# FSP-485.net
KiCad netlist of a schematic drawn in Altium Designer
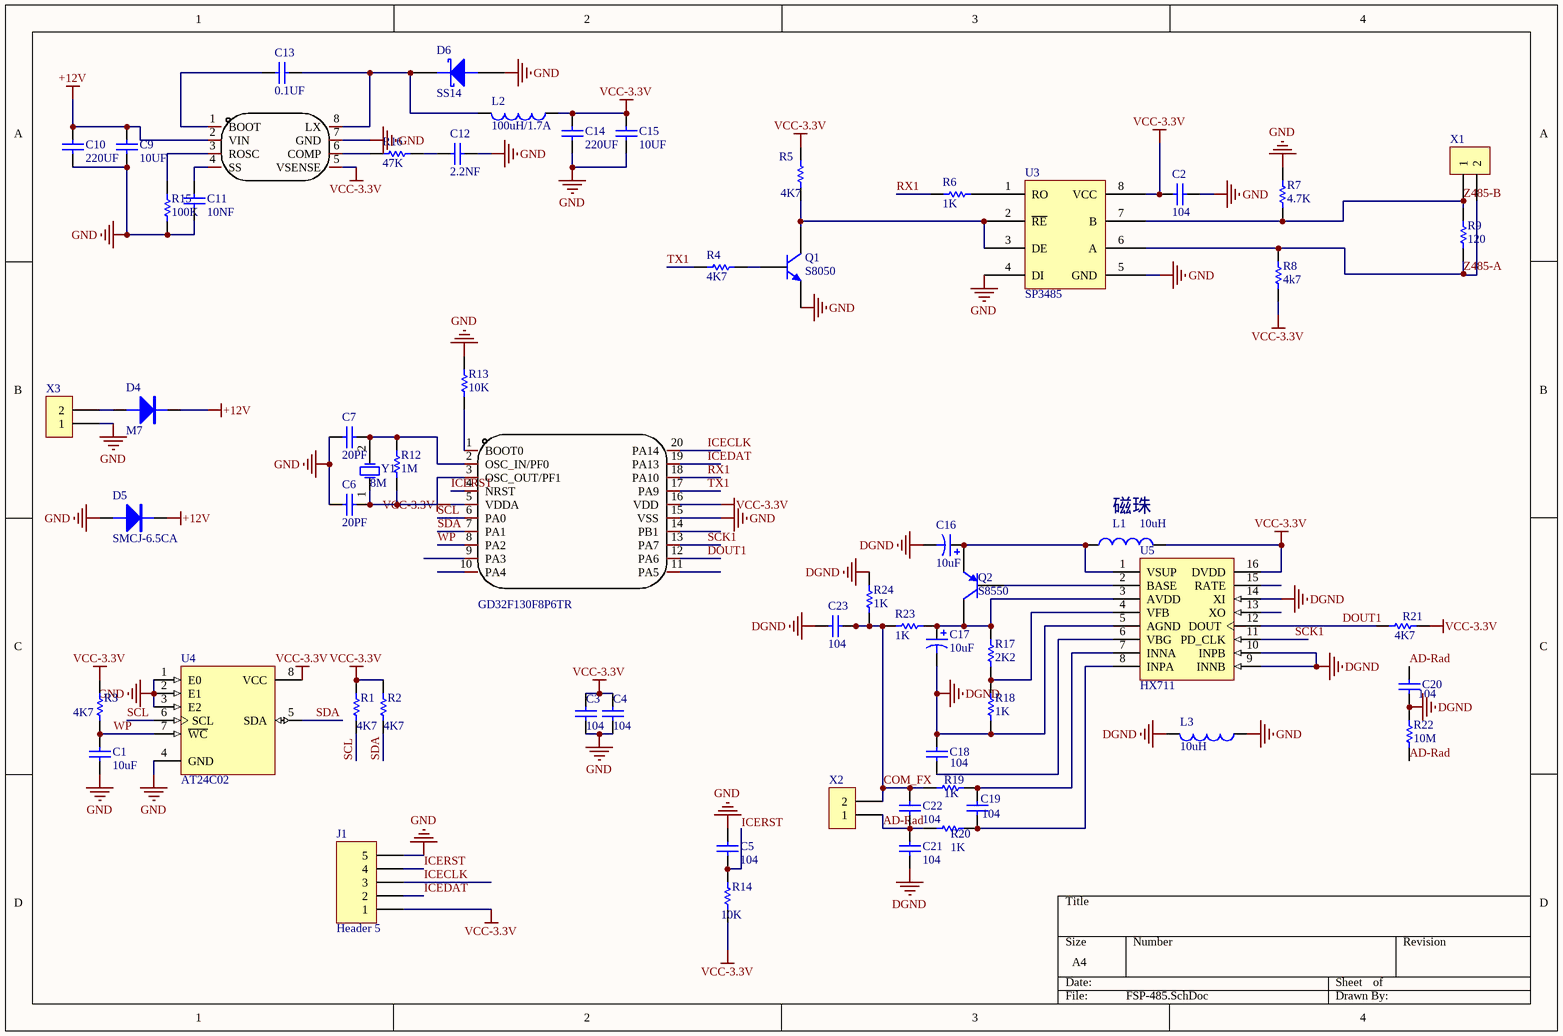
[diagram p0: FSP-485.SchDoc]

(export (version "E")
  (design (tool "Eeschema 10.0.6"))
  (components
    (comp (ref "C1")
      (value "10uF")
      (footprint "R0603")
      (description "Capacitor")
      (fields (field (name "Comment") "10uf") (field (name "PUBLISHER") "Altium Limited"))
      (libsource (lib "Miscellaneous Devices") (part "Cap"))
    )
    (comp (ref "C2")
      (value "104")
      (footprint "R0603")
      (description "Capacitor")
      (fields (field (name "PUBLISHER") "Altium Limited"))
      (libsource (lib "Miscellaneous Devices") (part "Cap"))
    )
    (comp (ref "C3")
      (value "104")
      (footprint "R0603")
      (description "Capacitor")
      (fields (field (name "PUBLISHER") "Altium Limited"))
      (libsource (lib "Miscellaneous Devices") (part "Cap"))
    )
    (comp (ref "C4")
      (value "104")
      (footprint "R0603")
      (description "Capacitor")
      (fields (field (name "PUBLISHER") "Altium Limited"))
      (libsource (lib "Miscellaneous Devices") (part "Cap"))
    )
    (comp (ref "C5")
      (value "104")
      (footprint "R0603")
      (description "Capacitor")
      (fields (field (name "PUBLISHER") "Altium Limited"))
      (libsource (lib "Miscellaneous Devices") (part "Cap"))
    )
    (comp (ref "C6")
      (value "20PF")
      (footprint "0805C")
      (description "Capacitor")
      (fields (field (name "PUBLISHER") "Altium Limited"))
      (libsource (lib "Wire Test") (part "Cap"))
    )
    (comp (ref "C7")
      (value "20PF")
      (footprint "0805C")
      (description "Capacitor")
      (fields (field (name "PUBLISHER") "Altium Limited"))
      (libsource (lib "Wire Test") (part "Cap"))
    )
    (comp (ref "C9")
      (value "10UF")
      (footprint "R0603")
      (description "Capacitor")
      (fields (field (name "PUBLISHER") "Altium Limited"))
      (libsource (lib "Wire Test") (part "Cap"))
    )
    (comp (ref "C10")
      (value "220UF")
      (footprint "CAP+_47UF_5X5")
      (description "Capacitor")
      (fields (field (name "PUBLISHER") "Altium Limited"))
      (libsource (lib "Wire Test") (part "Cap"))
    )
    (comp (ref "C11")
      (value "10NF")
      (footprint "R0603")
      (description "Capacitor")
      (fields (field (name "PUBLISHER") "Altium Limited"))
      (libsource (lib "Wire Test") (part "Cap"))
    )
    (comp (ref "C12")
      (value "2.2NF")
      (footprint "R0603")
      (description "Capacitor")
      (fields (field (name "PUBLISHER") "Altium Limited"))
      (libsource (lib "Wire Test") (part "Cap"))
    )
    (comp (ref "C13")
      (value "0.1UF")
      (footprint "R0603")
      (description "Capacitor")
      (fields (field (name "PUBLISHER") "Altium Limited"))
      (libsource (lib "Wire Test") (part "Cap"))
    )
    (comp (ref "C14")
      (value "220UF")
      (footprint "DAN-DIAN-RONG-1210")
      (description "Capacitor")
      (fields (field (name "PUBLISHER") "Altium Limited"))
      (libsource (lib "Wire Test") (part "Cap"))
    )
    (comp (ref "C15")
      (value "10UF")
      (footprint "R0603")
      (description "Capacitor")
      (fields (field (name "PUBLISHER") "Altium Limited"))
      (libsource (lib "Wire Test") (part "Cap"))
    )
    (comp (ref "C16")
      (value "10uF")
      (footprint "R0603")
      (description "Polarized Capacitor (Surface Mount)")
      (fields (field (name "Comment") "10uf") (field (name "PUBLISHER") "Altium Limited"))
      (libsource (lib "Miscellaneous Devices") (part "Cap Pol3"))
    )
    (comp (ref "C17")
      (value "10uF")
      (footprint "R0603")
      (description "Polarized Capacitor (Surface Mount)")
      (fields (field (name "Comment") "10uf") (field (name "PUBLISHER") "Altium Limited"))
      (libsource (lib "Miscellaneous Devices") (part "Cap Pol3"))
    )
    (comp (ref "C18")
      (value "104")
      (footprint "R0603")
      (description "Capacitor")
      (fields (field (name "PUBLISHER") "Altium Limited"))
      (libsource (lib "Miscellaneous Devices") (part "Cap"))
    )
    (comp (ref "C19")
      (value "104")
      (footprint "R0603")
      (description "Capacitor")
      (fields (field (name "PUBLISHER") "Altium Limited"))
      (libsource (lib "Miscellaneous Devices") (part "Cap"))
    )
    (comp (ref "C20")
      (value "104")
      (footprint "R0603")
      (description "Capacitor")
      (fields (field (name "PUBLISHER") "Altium Limited"))
      (libsource (lib "Miscellaneous Devices") (part "Cap"))
    )
    (comp (ref "C21")
      (value "104")
      (footprint "R0603")
      (description "Capacitor")
      (fields (field (name "PUBLISHER") "Altium Limited"))
      (libsource (lib "Miscellaneous Devices") (part "Cap"))
    )
    (comp (ref "C22")
      (value "104")
      (footprint "R0603")
      (description "Capacitor")
      (fields (field (name "PUBLISHER") "Altium Limited"))
      (libsource (lib "Miscellaneous Devices") (part "Cap"))
    )
    (comp (ref "C23")
      (value "104")
      (footprint "R0603")
      (description "Capacitor")
      (fields (field (name "PUBLISHER") "Altium Limited"))
      (libsource (lib "Miscellaneous Devices") (part "Cap"))
    )
    (comp (ref "D4")
      (value "M7")
      (footprint "DIODE")
      (description "Diode")
      (libsource (lib "*") (part "DIODE"))
    )
    (comp (ref "D5")
      (value "SMCJ-6.5CA")
      (footprint "DIODE")
      (description "Diode")
      (libsource (lib "*") (part "DIODE"))
    )
    (comp (ref "D6")
      (value "SS14")
      (footprint "DIODE")
      (description "Schottky Diode")
      (libsource (lib "*") (part "DIODE SCHOTTKY"))
    )
    (comp (ref "J1")
      (value "Header 5")
      (footprint "HDR1X5")
      (description "Header, 5-Pin")
      (fields (field (name "PUBLISHER") "Altium Limited"))
      (libsource (lib "Miscellaneous Connectors") (part "Header 5"))
    )
    (comp (ref "L1")
      (value "10uH")
      (footprint "R0603")
      (description "Inductor")
      (fields (field (name "PUBLISHER") "Altium Limited"))
      (libsource (lib "") (part "Inductor_1"))
    )
    (comp (ref "L2")
      (value "100uH/1.7A")
      (footprint "SMD-6*6MM")
      (description "Inductor")
      (fields (field (name "PUBLISHER") "Altium Limited"))
      (libsource (lib "Miscellaneous Devices") (part "Inductor"))
    )
    (comp (ref "L3")
      (value "10uH")
      (footprint "R0603")
      (description "Inductor")
      (fields (field (name "PUBLISHER") "Altium Limited"))
      (libsource (lib "Miscellaneous Devices") (part "Inductor"))
    )
    (comp (ref "Q1")
      (value "S8050")
      (footprint "Q8050")
      (description "NPN General Purpose Amplifier")
      (fields (field (name "PUBLISHER") "Altium Limited"))
      (libsource (lib "*") (part "2N3904"))
    )
    (comp (ref "Q2")
      (value "S8550")
      (footprint "Q8550")
      (description "PNP General Purpose Amplifier")
      (fields (field (name "PUBLISHER") "Altium Limited"))
      (libsource (lib "Miscellaneous Devices") (part "2N3906"))
    )
    (comp (ref "R1")
      (value "4K7")
      (footprint "R0603")
      (description "Resistor")
      (fields (field (name "PUBLISHER") "Altium Limited"))
      (libsource (lib "Wire Test") (part "Res1"))
    )
    (comp (ref "R2")
      (value "4K7")
      (footprint "R0603")
      (description "Resistor")
      (fields (field (name "PUBLISHER") "Altium Limited"))
      (libsource (lib "Wire Test") (part "Res1"))
    )
    (comp (ref "R3")
      (value "4K7")
      (footprint "R0603")
      (description "Resistor")
      (fields (field (name "PUBLISHER") "Altium Limited"))
      (libsource (lib "Wire Test") (part "Res1"))
    )
    (comp (ref "R4")
      (value "4K7")
      (footprint "R0603")
      (description "Resistor")
      (fields (field (name "PUBLISHER") "Altium Limited"))
      (libsource (lib "*") (part "Res1"))
    )
    (comp (ref "R5")
      (value "4K7")
      (footprint "R0603")
      (description "Resistor")
      (fields (field (name "PUBLISHER") "Altium Limited"))
      (libsource (lib "*") (part "Res1"))
    )
    (comp (ref "R6")
      (value "1K")
      (footprint "R0603")
      (description "Resistor")
      (fields (field (name "PUBLISHER") "Altium Limited"))
      (libsource (lib "*") (part "Res1"))
    )
    (comp (ref "R7")
      (value "4.7K")
      (footprint "R0603")
      (description "Resistor")
      (fields (field (name "Comment") "4K7") (field (name "PUBLISHER") "Altium Limited"))
      (libsource (lib "*") (part "Res1"))
    )
    (comp (ref "R8")
      (value "4k7")
      (footprint "R0603")
      (description "Resistor")
      (fields (field (name "Comment") "4K7") (field (name "PUBLISHER") "Altium Limited"))
      (libsource (lib "*") (part "Res1"))
    )
    (comp (ref "R9")
      (value "120")
      (footprint "R0603")
      (description "Resistor")
      (fields (field (name "PUBLISHER") "Altium Limited"))
      (libsource (lib "*") (part "Res1"))
    )
    (comp (ref "R12")
      (value "1M")
      (footprint "R0603")
      (description "Resistor")
      (fields (field (name "PUBLISHER") "Altium Limited"))
      (libsource (lib "Wire Test") (part "Res1"))
    )
    (comp (ref "R13")
      (value "10K")
      (footprint "R0603")
      (description "Resistor")
      (fields (field (name "PUBLISHER") "Altium Limited"))
      (libsource (lib "Wire Test") (part "Res1"))
    )
    (comp (ref "R14")
      (value "10K")
      (footprint "R0603")
      (description "Resistor")
      (fields (field (name "PUBLISHER") "Altium Limited"))
      (libsource (lib "*") (part "Res1"))
    )
    (comp (ref "R15")
      (value "100K")
      (footprint "R0603")
      (description "Resistor")
      (fields (field (name "PUBLISHER") "Altium Limited"))
      (libsource (lib "Wire Test") (part "Res1"))
    )
    (comp (ref "R16")
      (value "47K")
      (footprint "R0603")
      (description "Resistor")
      (fields (field (name "PUBLISHER") "Altium Limited"))
      (libsource (lib "Wire Test") (part "Res1"))
    )
    (comp (ref "R17")
      (value "2K2")
      (footprint "R0603")
      (description "Resistor")
      (fields (field (name "PUBLISHER") "Altium Limited"))
      (libsource (lib "Wire Test") (part "Res1"))
    )
    (comp (ref "R18")
      (value "1K")
      (footprint "R0603")
      (description "Resistor")
      (fields (field (name "PUBLISHER") "Altium Limited"))
      (libsource (lib "Wire Test") (part "Res1"))
    )
    (comp (ref "R19")
      (value "1K")
      (footprint "R0603")
      (description "Resistor")
      (fields (field (name "PUBLISHER") "Altium Limited"))
      (libsource (lib "Wire Test") (part "Res1"))
    )
    (comp (ref "R20")
      (value "1K")
      (footprint "R0603")
      (description "Resistor")
      (fields (field (name "PUBLISHER") "Altium Limited"))
      (libsource (lib "Wire Test") (part "Res1"))
    )
    (comp (ref "R21")
      (value "4K7")
      (footprint "R0603")
      (description "Resistor")
      (fields (field (name "PUBLISHER") "Altium Limited"))
      (libsource (lib "Wire Test") (part "Res1"))
    )
    (comp (ref "R22")
      (value "10M")
      (footprint "R0603")
      (description "Resistor")
      (fields (field (name "PUBLISHER") "Altium Limited"))
      (libsource (lib "Wire Test") (part "Res1"))
    )
    (comp (ref "R23")
      (value "1K")
      (footprint "R0603")
      (description "Resistor")
      (fields (field (name "PUBLISHER") "Altium Limited"))
      (libsource (lib "Wire Test") (part "Res1"))
    )
    (comp (ref "R24")
      (value "1K")
      (footprint "R0603")
      (description "Resistor")
      (fields (field (name "PUBLISHER") "Altium Limited"))
      (libsource (lib "Wire Test") (part "Res1"))
    )
    (comp (ref "U1")
      (value "GD32F130F8P6TR")
      (footprint "GD32F130F8P6TR")
      (fields (field (name "MANUFACTURER") "GigaDevice(兆易创新)"))
      (libsource (lib "altium-import") (part "root_0_GD32F130F8P6TR_"))
    )
    (comp (ref "U2")
      (value "TPS5403DR")
      (footprint "TPS5403DR")
      (fields (field (name "MANUFACTURER") "TI(德州仪器)"))
      (libsource (lib "altium-import") (part "root_0_TPS5403DR_"))
    )
    (comp (ref "U3") (value "SP3485") (footprint "MAX485") (libsource (lib "金龙107原理图封装库") (part "MAX485")))
    (comp (ref "U4")
      (value "AT24C02")
      (footprint "AT24C02")
      (description "2Kbit Serial I睠 Bus EEPROM")
      (fields (field (name "PUBLISHER") "Altium Limited"))
      (libsource (lib "ST Memory EEPROM Serial") (part "M24C02BN6"))
    )
    (comp (ref "U5") (value "HX711") (footprint "HX711") (libsource (lib "微电脑分装机_1") (part "HX711")))
    (comp (ref "X1")
      (value "~")
      (footprint "CON-2.54mm*2")
      (description "Connector")
      (libsource (lib "*") (part "CON2"))
    )
    (comp (ref "X2")
      (value "~")
      (footprint "CON-2.54mm*2")
      (description "Connector")
      (libsource (lib "") (part "CON2_1"))
    )
    (comp (ref "X3")
      (value "~")
      (footprint "CON-2.54mm*2")
      (description "Connector")
      (libsource (lib "") (part "CON2_1"))
    )
    (comp (ref "Y1")
      (value "8M")
      (footprint "XTAL-T")
      (description "Crystal Oscillator")
      (fields (field (name "PUBLISHER") "Altium Limited"))
      (libsource (lib "Miscellaneous Devices") (part "XTAL"))
    )
  )
  (nets
    (net (code "1") (name "+12V") (class "Default")
      (node (ref "C10") (pin "1") (pinfunction "1_1") (pintype "passive"))
      (node (ref "C9") (pin "1") (pinfunction "1_1") (pintype "passive"))
      (node (ref "D4") (pin "2") (pinfunction "K_2") (pintype "passive"))
      (node (ref "D5") (pin "2") (pinfunction "K_2") (pintype "passive"))
      (node (ref "U2") (pin "2") (pinfunction "VIN_2") (pintype "passive"))
    )
    (net (code "2") (name "/AD-Rad") (class "Default")
      (node (ref "C20") (pin "1") (pinfunction "1_1") (pintype "passive"))
      (node (ref "C21") (pin "1") (pinfunction "1_1") (pintype "passive"))
      (node (ref "C22") (pin "1") (pinfunction "1_1") (pintype "passive"))
      (node (ref "R20") (pin "1") (pinfunction "1_1") (pintype "passive"))
      (node (ref "R22") (pin "1") (pinfunction "1_1") (pintype "passive"))
      (node (ref "X2") (pin "1") (pinfunction "1_1") (pintype "passive"))
    )
    (net (code "3") (name "/COM_FX") (class "Default")
      (node (ref "C22") (pin "2") (pinfunction "2_2") (pintype "passive"))
      (node (ref "C23") (pin "1") (pinfunction "1_1") (pintype "passive"))
      (node (ref "R19") (pin "1") (pinfunction "1_1") (pintype "passive"))
      (node (ref "R23") (pin "1") (pinfunction "1_1") (pintype "passive"))
      (node (ref "R24") (pin "2") (pinfunction "2_2") (pintype "passive"))
      (node (ref "X2") (pin "2") (pinfunction "2_2") (pintype "passive"))
    )
    (net (code "4") (name "/DOUT1") (class "Default")
      (node (ref "R21") (pin "2") (pinfunction "2_2") (pintype "passive"))
      (node (ref "U1") (pin "12") (pinfunction "PA6_12") (pintype "passive"))
      (node (ref "U5") (pin "12") (pinfunction "DOUT_12") (pintype "passive"))
    )
    (net (code "5") (name "/ICECLK") (class "Default")
      (node (ref "J1") (pin "3") (pinfunction "3_3") (pintype "passive"))
      (node (ref "U1") (pin "20") (pinfunction "PA14_20") (pintype "passive"))
    )
    (net (code "6") (name "/ICEDAT") (class "Default")
      (node (ref "J1") (pin "2") (pinfunction "2_2") (pintype "passive"))
      (node (ref "U1") (pin "19") (pinfunction "PA13_19") (pintype "passive"))
    )
    (net (code "7") (name "/ICERST") (class "Default")
      (node (ref "C5") (pin "1") (pinfunction "1_1") (pintype "passive"))
      (node (ref "J1") (pin "4") (pinfunction "4_4") (pintype "passive"))
      (node (ref "R14") (pin "1") (pinfunction "1_1") (pintype "passive"))
      (node (ref "U1") (pin "4") (pinfunction "NRST_4") (pintype "passive"))
    )
    (net (code "8") (name "/RX1") (class "Default")
      (node (ref "R6") (pin "2") (pinfunction "2_2") (pintype "passive"))
      (node (ref "U1") (pin "18") (pinfunction "PA10_18") (pintype "passive"))
    )
    (net (code "9") (name "/SCK1") (class "Default")
      (node (ref "U1") (pin "13") (pinfunction "PA7_13") (pintype "passive"))
      (node (ref "U5") (pin "11") (pinfunction "PD_CLK_11") (pintype "input"))
    )
    (net (code "10") (name "/SCL") (class "Default")
      (node (ref "R1") (pin "1") (pinfunction "1_1") (pintype "passive"))
      (node (ref "U1") (pin "6") (pinfunction "PA0_6") (pintype "passive"))
      (node (ref "U4") (pin "6") (pinfunction "SCL_6") (pintype "input"))
    )
    (net (code "11") (name "/SDA") (class "Default")
      (node (ref "R2") (pin "1") (pinfunction "1_1") (pintype "passive"))
      (node (ref "U1") (pin "7") (pinfunction "PA1_7") (pintype "passive"))
      (node (ref "U4") (pin "5") (pinfunction "SDA_5") (pintype "bidirectional"))
    )
    (net (code "12") (name "/TX1") (class "Default")
      (node (ref "R4") (pin "1") (pinfunction "1_1") (pintype "passive"))
      (node (ref "U1") (pin "17") (pinfunction "PA9_17") (pintype "passive"))
    )
    (net (code "13") (name "/WP") (class "Default")
      (node (ref "C1") (pin "2") (pinfunction "2_2") (pintype "passive"))
      (node (ref "R3") (pin "1") (pinfunction "1_1") (pintype "passive"))
      (node (ref "U1") (pin "8") (pinfunction "PA2_8") (pintype "passive"))
      (node (ref "U4") (pin "7") (pinfunction "~{WC}_7") (pintype "input"))
    )
    (net (code "14") (name "/Z485-A") (class "Default")
      (node (ref "R8") (pin "1") (pinfunction "1_1") (pintype "passive"))
      (node (ref "R9") (pin "2") (pinfunction "2_2") (pintype "passive"))
      (node (ref "U3") (pin "6") (pinfunction "A_6") (pintype "open_emitter"))
      (node (ref "X1") (pin "2") (pinfunction "2_2") (pintype "passive"))
    )
    (net (code "15") (name "/Z485-B") (class "Default")
      (node (ref "R7") (pin "1") (pinfunction "1_1") (pintype "passive"))
      (node (ref "R9") (pin "1") (pinfunction "1_1") (pintype "passive"))
      (node (ref "U3") (pin "7") (pinfunction "B_7") (pintype "open_emitter"))
      (node (ref "X1") (pin "1") (pinfunction "1_1") (pintype "passive"))
    )
    (net (code "16") (name "DGND") (class "Default")
      (node (ref "C16") (pin "2") (pinfunction "2_2") (pintype "passive"))
      (node (ref "C17") (pin "2") (pinfunction "2_2") (pintype "passive"))
      (node (ref "C18") (pin "2") (pinfunction "2_2") (pintype "passive"))
      (node (ref "C20") (pin "2") (pinfunction "2_2") (pintype "passive"))
      (node (ref "C21") (pin "2") (pinfunction "2_2") (pintype "passive"))
      (node (ref "C23") (pin "2") (pinfunction "2_2") (pintype "passive"))
      (node (ref "L3") (pin "1") (pinfunction "1_1") (pintype "passive"))
      (node (ref "R18") (pin "2") (pinfunction "2_2") (pintype "passive"))
      (node (ref "R22") (pin "2") (pinfunction "2_2") (pintype "passive"))
      (node (ref "R24") (pin "1") (pinfunction "1_1") (pintype "passive"))
      (node (ref "U5") (pin "10") (pinfunction "INPB_10") (pintype "input"))
      (node (ref "U5") (pin "14") (pinfunction "XI_14") (pintype "input"))
      (node (ref "U5") (pin "5") (pinfunction "AGND_5") (pintype "tri_state"))
      (node (ref "U5") (pin "9") (pinfunction "INNB_9") (pintype "input"))
    )
    (net (code "17") (name "GND") (class "Default")
      (node (ref "C1") (pin "1") (pinfunction "1_1") (pintype "passive"))
      (node (ref "C10") (pin "2") (pinfunction "2_2") (pintype "passive"))
      (node (ref "C11") (pin "2") (pinfunction "2_2") (pintype "passive"))
      (node (ref "C12") (pin "2") (pinfunction "2_2") (pintype "passive"))
      (node (ref "C14") (pin "1") (pinfunction "1_1") (pintype "passive"))
      (node (ref "C15") (pin "2") (pinfunction "2_2") (pintype "passive"))
      (node (ref "C2") (pin "2") (pinfunction "2_2") (pintype "passive"))
      (node (ref "C3") (pin "2") (pinfunction "2_2") (pintype "passive"))
      (node (ref "C4") (pin "2") (pinfunction "2_2") (pintype "passive"))
      (node (ref "C5") (pin "2") (pinfunction "2_2") (pintype "passive"))
      (node (ref "C6") (pin "2") (pinfunction "2_2") (pintype "passive"))
      (node (ref "C7") (pin "2") (pinfunction "2_2") (pintype "passive"))
      (node (ref "C9") (pin "2") (pinfunction "2_2") (pintype "passive"))
      (node (ref "D5") (pin "1") (pinfunction "A_1") (pintype "passive"))
      (node (ref "D6") (pin "1") (pinfunction "A_1") (pintype "passive"))
      (node (ref "J1") (pin "5") (pinfunction "5_5") (pintype "passive"))
      (node (ref "L3") (pin "2") (pinfunction "2_2") (pintype "passive"))
      (node (ref "Q1") (pin "1") (pinfunction "E_1") (pintype "passive"))
      (node (ref "R13") (pin "2") (pinfunction "2_2") (pintype "passive"))
      (node (ref "R15") (pin "2") (pinfunction "2_2") (pintype "passive"))
      (node (ref "R7") (pin "2") (pinfunction "2_2") (pintype "passive"))
      (node (ref "U1") (pin "15") (pinfunction "VSS_15") (pintype "passive"))
      (node (ref "U2") (pin "7") (pinfunction "GND_7") (pintype "passive"))
      (node (ref "U3") (pin "4") (pinfunction "DI_4") (pintype "open_emitter"))
      (node (ref "U3") (pin "5") (pinfunction "GND_5") (pintype "passive"))
      (node (ref "U4") (pin "1") (pinfunction "E0_1") (pintype "input"))
      (node (ref "U4") (pin "2") (pinfunction "E1_2") (pintype "input"))
      (node (ref "U4") (pin "3") (pinfunction "E2_3") (pintype "input"))
      (node (ref "U4") (pin "4") (pinfunction "GND_4") (pintype "power_in"))
      (node (ref "X3") (pin "1") (pinfunction "1_1") (pintype "passive"))
    )
    (net (code "18") (name "Net-(C12-Pad1)") (class "Default")
      (node (ref "C12") (pin "1") (pinfunction "1_1") (pintype "passive"))
      (node (ref "R16") (pin "1") (pinfunction "1_1") (pintype "passive"))
    )
    (net (code "19") (name "Net-(D4-A)") (class "Default")
      (node (ref "D4") (pin "1") (pinfunction "A_1") (pintype "passive"))
      (node (ref "X3") (pin "2") (pinfunction "2_2") (pintype "passive"))
    )
    (net (code "20") (name "Net-(D6-K)") (class "Default")
      (node (ref "C13") (pin "2") (pinfunction "2_2") (pintype "passive"))
      (node (ref "D6") (pin "2") (pinfunction "K_2") (pintype "passive"))
      (node (ref "L2") (pin "1") (pinfunction "1_1") (pintype "passive"))
      (node (ref "U2") (pin "8") (pinfunction "LX_8") (pintype "passive"))
    )
    (net (code "21") (name "Net-(Q1-B)") (class "Default")
      (node (ref "Q1") (pin "2") (pinfunction "B_2") (pintype "passive"))
      (node (ref "R4") (pin "2") (pinfunction "2_2") (pintype "passive"))
    )
    (net (code "22") (name "Net-(Q1-C)") (class "Default")
      (node (ref "Q1") (pin "3") (pinfunction "C_3") (pintype "passive"))
      (node (ref "R5") (pin "2") (pinfunction "2_2") (pintype "passive"))
      (node (ref "U3") (pin "2") (pinfunction "~{RE}_2") (pintype "open_emitter"))
      (node (ref "U3") (pin "3") (pinfunction "DE_3") (pintype "open_emitter"))
    )
    (net (code "23") (name "Net-(Q2-B)") (class "Default")
      (node (ref "Q2") (pin "2") (pinfunction "B_2") (pintype "passive"))
      (node (ref "U5") (pin "2") (pinfunction "BASE_2") (pintype "tri_state"))
    )
    (net (code "24") (name "Net-(Q2-C)") (class "Default")
      (node (ref "C17") (pin "1") (pinfunction "1_1") (pintype "passive"))
      (node (ref "Q2") (pin "3") (pinfunction "C_3") (pintype "passive"))
      (node (ref "R17") (pin "1") (pinfunction "1_1") (pintype "passive"))
      (node (ref "R23") (pin "2") (pinfunction "2_2") (pintype "passive"))
      (node (ref "U5") (pin "3") (pinfunction "AVDD_3") (pintype "tri_state"))
    )
    (net (code "25") (name "Net-(Q2-E)") (class "Default")
      (node (ref "C16") (pin "1") (pinfunction "1_1") (pintype "passive"))
      (node (ref "L1") (pin "1") (pinfunction "1_1") (pintype "passive"))
      (node (ref "Q2") (pin "1") (pinfunction "E_1") (pintype "passive"))
      (node (ref "U5") (pin "1") (pinfunction "VSUP_1") (pintype "tri_state"))
    )
    (net (code "26") (name "Net-(U1-BOOT0)") (class "Default")
      (node (ref "R13") (pin "1") (pinfunction "1_1") (pintype "passive"))
      (node (ref "U1") (pin "1") (pinfunction "BOOT0_1") (pintype "passive"))
    )
    (net (code "27") (name "Net-(U1-OSC_IN{slash}PF0)") (class "Default")
      (node (ref "C7") (pin "1") (pinfunction "1_1") (pintype "passive"))
      (node (ref "R12") (pin "1") (pinfunction "1_1") (pintype "passive"))
      (node (ref "U1") (pin "2") (pinfunction "OSC_IN/PF0_2") (pintype "passive"))
      (node (ref "Y1") (pin "2") (pinfunction "OSC2_2") (pintype "passive"))
    )
    (net (code "28") (name "Net-(U1-OSC_OUT{slash}PF1)") (class "Default")
      (node (ref "C6") (pin "1") (pinfunction "1_1") (pintype "passive"))
      (node (ref "R12") (pin "2") (pinfunction "2_2") (pintype "passive"))
      (node (ref "U1") (pin "3") (pinfunction "OSC_OUT/PF1_3") (pintype "passive"))
      (node (ref "Y1") (pin "1") (pinfunction "OSC1_1") (pintype "passive"))
    )
    (net (code "29") (name "Net-(U2-BOOT)") (class "Default")
      (node (ref "C13") (pin "1") (pinfunction "1_1") (pintype "passive"))
      (node (ref "U2") (pin "1") (pinfunction "BOOT_1") (pintype "passive"))
    )
    (net (code "30") (name "Net-(U2-COMP)") (class "Default")
      (node (ref "R16") (pin "2") (pinfunction "2_2") (pintype "passive"))
      (node (ref "U2") (pin "6") (pinfunction "COMP_6") (pintype "passive"))
    )
    (net (code "31") (name "Net-(U2-ROSC)") (class "Default")
      (node (ref "R15") (pin "1") (pinfunction "1_1") (pintype "passive"))
      (node (ref "U2") (pin "3") (pinfunction "ROSC_3") (pintype "passive"))
    )
    (net (code "32") (name "Net-(U2-SS)") (class "Default")
      (node (ref "C11") (pin "1") (pinfunction "1_1") (pintype "passive"))
      (node (ref "U2") (pin "4") (pinfunction "SS_4") (pintype "passive"))
    )
    (net (code "33") (name "Net-(U3-RO)") (class "Default")
      (node (ref "R6") (pin "1") (pinfunction "1_1") (pintype "passive"))
      (node (ref "U3") (pin "1") (pinfunction "RO_1") (pintype "open_emitter"))
    )
    (net (code "34") (name "Net-(U5-INNA)") (class "Default")
      (node (ref "C19") (pin "2") (pinfunction "2_2") (pintype "passive"))
      (node (ref "R19") (pin "2") (pinfunction "2_2") (pintype "passive"))
      (node (ref "U5") (pin "7") (pinfunction "INNA_7") (pintype "tri_state"))
    )
    (net (code "35") (name "Net-(U5-INPA)") (class "Default")
      (node (ref "C19") (pin "1") (pinfunction "1_1") (pintype "passive"))
      (node (ref "R20") (pin "2") (pinfunction "2_2") (pintype "passive"))
      (node (ref "U5") (pin "8") (pinfunction "INPA_8") (pintype "power_in"))
    )
    (net (code "36") (name "Net-(U5-VBG)") (class "Default")
      (node (ref "C18") (pin "1") (pinfunction "1_1") (pintype "passive"))
      (node (ref "U5") (pin "6") (pinfunction "VBG_6") (pintype "tri_state"))
    )
    (net (code "37") (name "Net-(U5-VFB)") (class "Default")
      (node (ref "R17") (pin "2") (pinfunction "2_2") (pintype "passive"))
      (node (ref "R18") (pin "1") (pinfunction "1_1") (pintype "passive"))
      (node (ref "U5") (pin "4") (pinfunction "VFB_4") (pintype "tri_state"))
    )
    (net (code "38") (name "VCC-3.3V") (class "Default")
      (node (ref "C14") (pin "2") (pinfunction "2_2") (pintype "passive"))
      (node (ref "C15") (pin "1") (pinfunction "1_1") (pintype "passive"))
      (node (ref "C2") (pin "1") (pinfunction "1_1") (pintype "passive"))
      (node (ref "C3") (pin "1") (pinfunction "1_1") (pintype "passive"))
      (node (ref "C4") (pin "1") (pinfunction "1_1") (pintype "passive"))
      (node (ref "J1") (pin "1") (pinfunction "1_1") (pintype "passive"))
      (node (ref "L1") (pin "2") (pinfunction "2_2") (pintype "passive"))
      (node (ref "L2") (pin "2") (pinfunction "2_2") (pintype "passive"))
      (node (ref "R1") (pin "2") (pinfunction "2_2") (pintype "passive"))
      (node (ref "R14") (pin "2") (pinfunction "2_2") (pintype "passive"))
      (node (ref "R2") (pin "2") (pinfunction "2_2") (pintype "passive"))
      (node (ref "R21") (pin "1") (pinfunction "1_1") (pintype "passive"))
      (node (ref "R3") (pin "2") (pinfunction "2_2") (pintype "passive"))
      (node (ref "R5") (pin "1") (pinfunction "1_1") (pintype "passive"))
      (node (ref "R8") (pin "2") (pinfunction "2_2") (pintype "passive"))
      (node (ref "U1") (pin "16") (pinfunction "VDD_16") (pintype "passive"))
      (node (ref "U1") (pin "5") (pinfunction "VDDA_5") (pintype "passive"))
      (node (ref "U2") (pin "5") (pinfunction "VSENSE_5") (pintype "passive"))
      (node (ref "U3") (pin "8") (pinfunction "VCC_8") (pintype "passive"))
      (node (ref "U4") (pin "8") (pinfunction "VCC_8") (pintype "power_in"))
      (node (ref "U5") (pin "16") (pinfunction "DVDD_16") (pintype "power_in"))
    )
    (net (code "39") (name "unconnected-(U1-PA3-Pad9)") (class "Default")
      (node (ref "U1") (pin "9") (pinfunction "PA3_9") (pintype "passive"))
    )
    (net (code "40") (name "unconnected-(U1-PA4-Pad10)") (class "Default")
      (node (ref "U1") (pin "10") (pinfunction "PA4_10") (pintype "passive"))
    )
    (net (code "41") (name "unconnected-(U1-PA5-Pad11)") (class "Default")
      (node (ref "U1") (pin "11") (pinfunction "PA5_11") (pintype "passive"))
    )
    (net (code "42") (name "unconnected-(U1-PB1-Pad14)") (class "Default")
      (node (ref "U1") (pin "14") (pinfunction "PB1_14") (pintype "passive"))
    )
    (net (code "43") (name "unconnected-(U5-RATE-Pad15)") (class "Default")
      (node (ref "U5") (pin "15") (pinfunction "RATE_15") (pintype "tri_state"))
    )
    (net (code "44") (name "unconnected-(U5-XO-Pad13)") (class "Default")
      (node (ref "U5") (pin "13") (pinfunction "XO_13") (pintype "input"))
    )
  )
)
